# SEAx_connector.net
KiCad netlist of a schematic drawn in Altium Designer
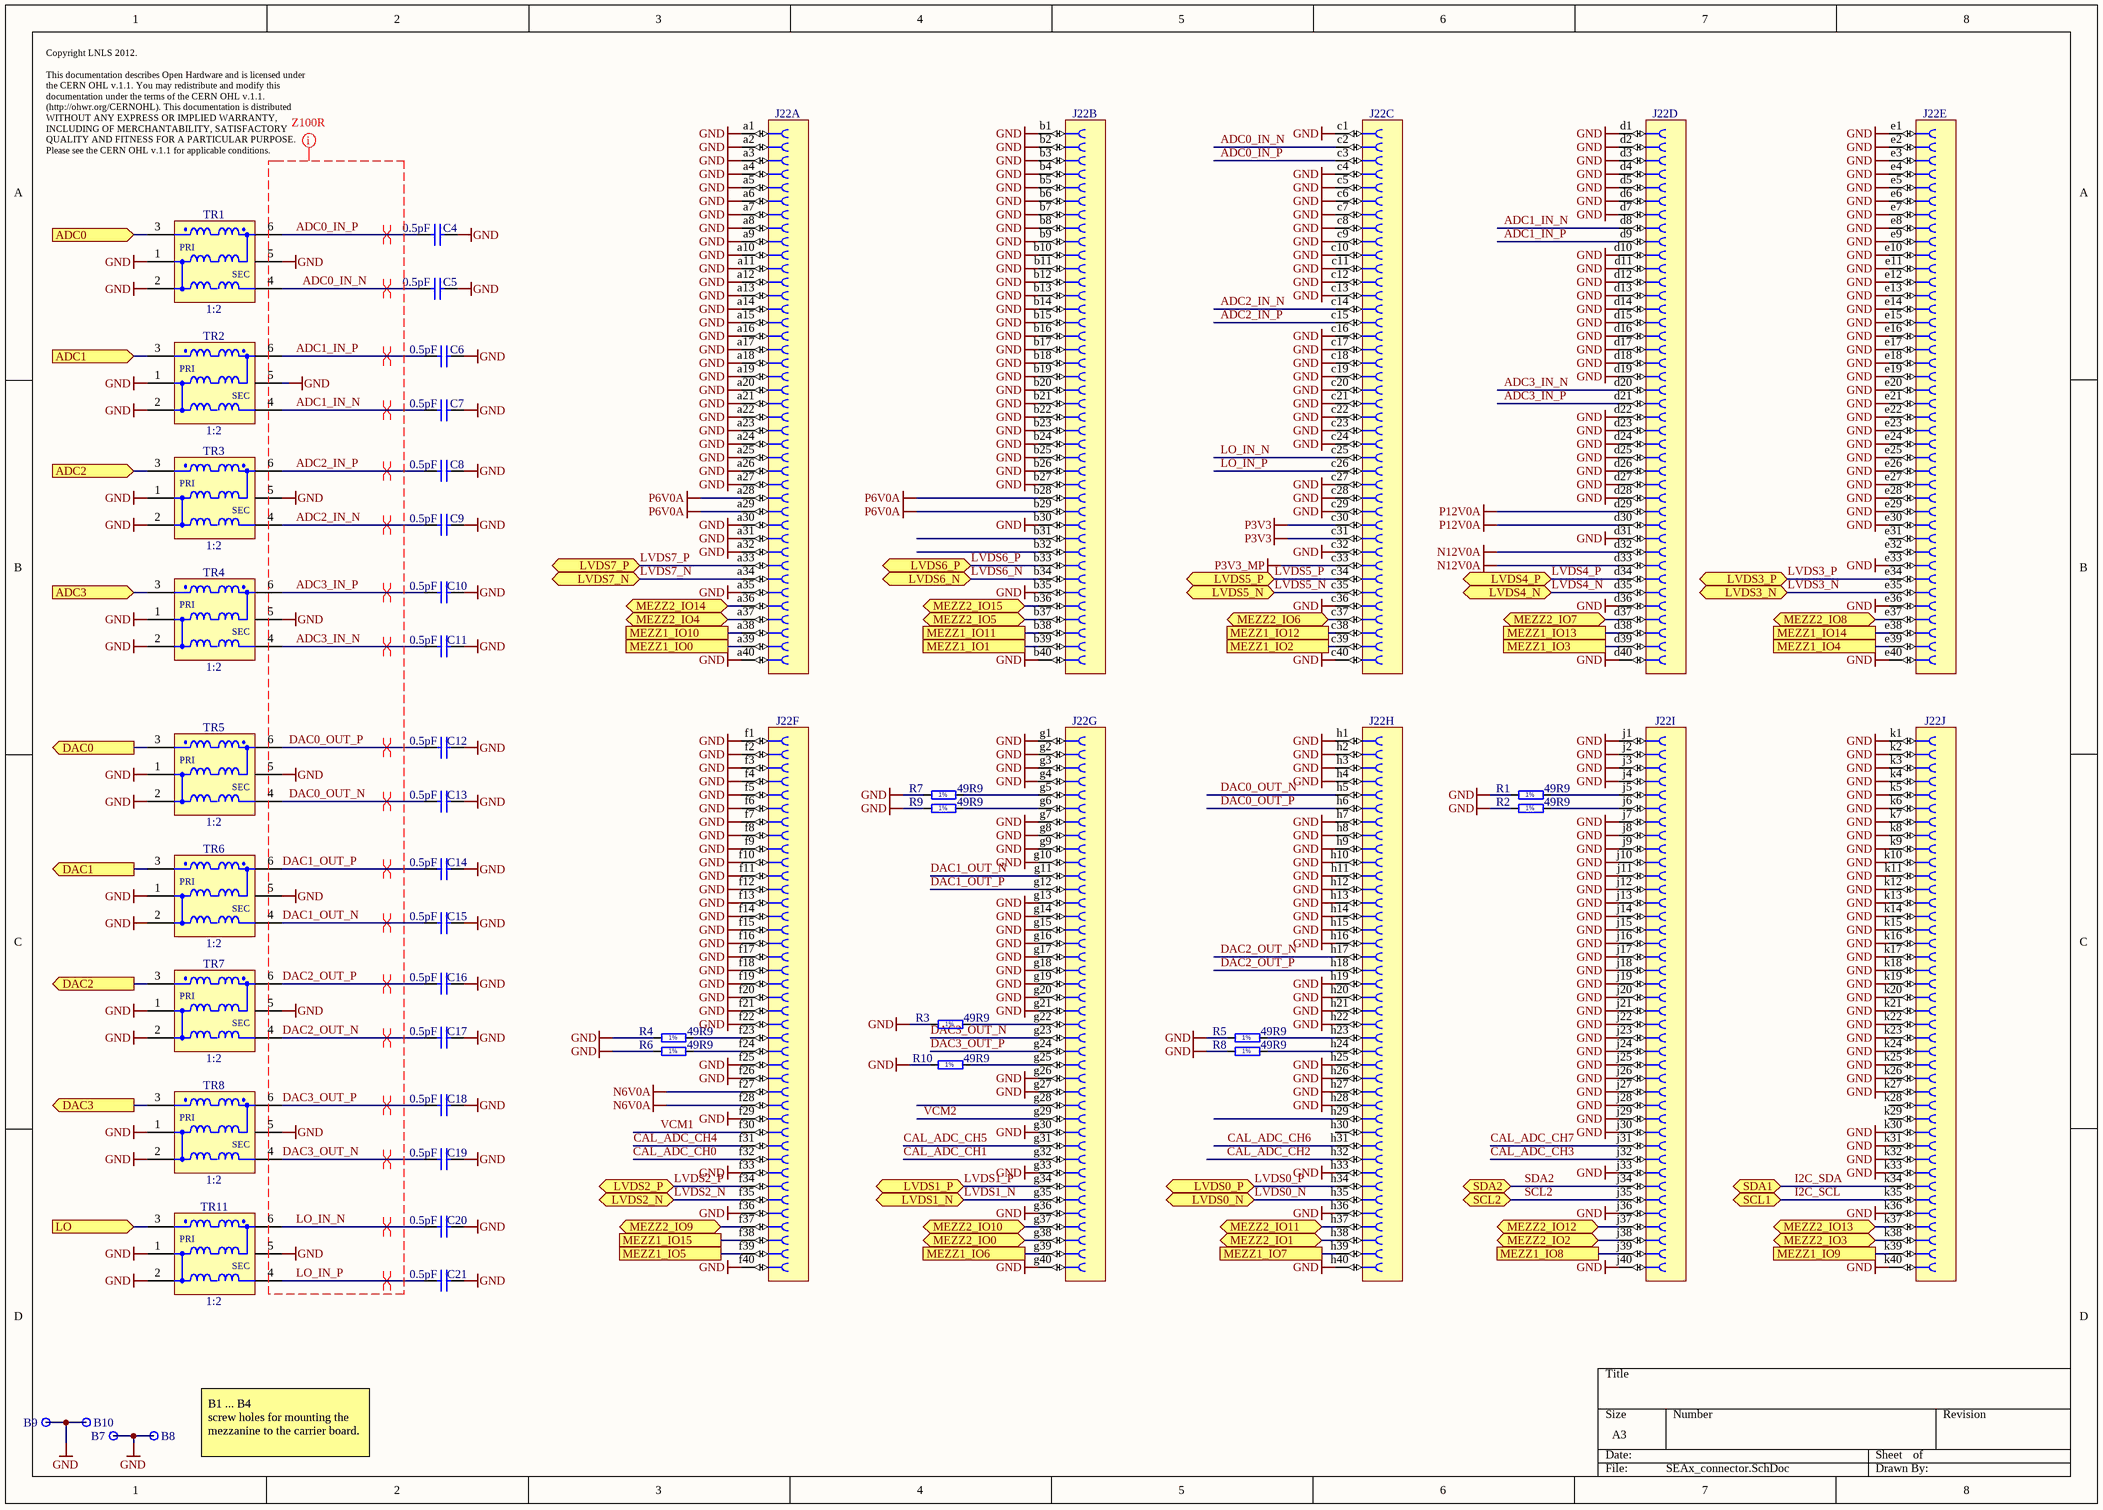
[diagram p0: SEAx_connector.SchDoc]

(export (version "E")
  (design (tool "Eeschema 10.0.6"))
  (components
    (comp (ref "B7")
      (value "Plated Hole")
      (footprint "MTG270_500")
      (description "Single Terminal Socket")
      (fields (field (name "PART NUMBER") "PLATED_HOLE2.7_PAD5.0") (field (name "AUTHOR") "CERN DEM JMW"))
      (libsource (lib "Eletro-mechanical") (part "Single Terminal Socket"))
    )
    (comp (ref "B8")
      (value "Plated Hole")
      (footprint "MTG270_500")
      (description "Single Terminal Socket")
      (fields (field (name "PART NUMBER") "PLATED_HOLE2.7_PAD5.0") (field (name "AUTHOR") "CERN DEM JMW"))
      (libsource (lib "Eletro-mechanical") (part "Single Terminal Socket"))
    )
    (comp (ref "B9")
      (value "Plated Hole")
      (footprint "MTG270_500")
      (description "Single Terminal Socket")
      (fields (field (name "PART NUMBER") "PLATED_HOLE2.7_PAD5.0") (field (name "AUTHOR") "CERN DEM JMW"))
      (libsource (lib "Eletro-mechanical") (part "Single Terminal Socket"))
    )
    (comp (ref "B10")
      (value "Plated Hole")
      (footprint "MTG270_500")
      (description "Single Terminal Socket")
      (fields (field (name "PART NUMBER") "PLATED_HOLE2.7_PAD5.0") (field (name "AUTHOR") "CERN DEM JMW"))
      (libsource (lib "Eletro-mechanical") (part "Single Terminal Socket"))
    )
    (comp (ref "C4")
      (value "0.5pF")
      (footprint "CAPC1005X50N")
      (description "Non-polarised capacitor")
      (fields
        (field (name "PART NUMBER") "CC0402_0.5PF_25V_0.05PF_AVX_04023J0R5ABSTR")
        (field (name "VOLTAGE") "25V")
        (field (name "AUTHOR") "CERN DEM JLC")
      )
      (libsource (lib "Capacitors") (part "Capacitor - non polarized"))
    )
    (comp (ref "C5")
      (value "0.5pF")
      (footprint "CAPC1005X50N")
      (description "Non-polarised capacitor")
      (fields
        (field (name "PART NUMBER") "CC0402_0.5PF_25V_0.05PF_AVX_04023J0R5ABSTR")
        (field (name "VOLTAGE") "25V")
        (field (name "AUTHOR") "CERN DEM JLC")
      )
      (libsource (lib "Capacitors") (part "Capacitor - non polarized"))
    )
    (comp (ref "C6")
      (value "0.5pF")
      (footprint "CAPC1005X50N")
      (description "Non-polarised capacitor")
      (fields
        (field (name "PART NUMBER") "CC0402_0.5PF_25V_0.05PF_AVX_04023J0R5ABSTR")
        (field (name "VOLTAGE") "25V")
        (field (name "AUTHOR") "CERN DEM JLC")
      )
      (libsource (lib "Capacitors") (part "Capacitor - non polarized"))
    )
    (comp (ref "C7")
      (value "0.5pF")
      (footprint "CAPC1005X50N")
      (description "Non-polarised capacitor")
      (fields
        (field (name "PART NUMBER") "CC0402_0.5PF_25V_0.05PF_AVX_04023J0R5ABSTR")
        (field (name "VOLTAGE") "25V")
        (field (name "AUTHOR") "CERN DEM JLC")
      )
      (libsource (lib "Capacitors") (part "Capacitor - non polarized"))
    )
    (comp (ref "C8")
      (value "0.5pF")
      (footprint "CAPC1005X50N")
      (description "Non-polarised capacitor")
      (fields
        (field (name "PART NUMBER") "CC0402_0.5PF_25V_0.05PF_AVX_04023J0R5ABSTR")
        (field (name "VOLTAGE") "25V")
        (field (name "AUTHOR") "CERN DEM JLC")
      )
      (libsource (lib "Capacitors") (part "Capacitor - non polarized"))
    )
    (comp (ref "C9")
      (value "0.5pF")
      (footprint "CAPC1005X50N")
      (description "Non-polarised capacitor")
      (fields
        (field (name "PART NUMBER") "CC0402_0.5PF_25V_0.05PF_AVX_04023J0R5ABSTR")
        (field (name "VOLTAGE") "25V")
        (field (name "AUTHOR") "CERN DEM JLC")
      )
      (libsource (lib "Capacitors") (part "Capacitor - non polarized"))
    )
    (comp (ref "C10")
      (value "0.5pF")
      (footprint "CAPC1005X50N")
      (description "Non-polarised capacitor")
      (fields
        (field (name "PART NUMBER") "CC0402_0.5PF_25V_0.05PF_AVX_04023J0R5ABSTR")
        (field (name "VOLTAGE") "25V")
        (field (name "AUTHOR") "CERN DEM JLC")
      )
      (libsource (lib "Capacitors") (part "Capacitor - non polarized"))
    )
    (comp (ref "C11")
      (value "0.5pF")
      (footprint "CAPC1005X50N")
      (description "Non-polarised capacitor")
      (fields
        (field (name "PART NUMBER") "CC0402_0.5PF_25V_0.05PF_AVX_04023J0R5ABSTR")
        (field (name "VOLTAGE") "25V")
        (field (name "AUTHOR") "CERN DEM JLC")
      )
      (libsource (lib "Capacitors") (part "Capacitor - non polarized"))
    )
    (comp (ref "C12")
      (value "0.5pF")
      (footprint "CAPC1005X50N")
      (description "Non-polarised capacitor")
      (fields
        (field (name "PART NUMBER") "CC0402_0.5PF_25V_0.05PF_AVX_04023J0R5ABSTR")
        (field (name "VOLTAGE") "25V")
        (field (name "AUTHOR") "CERN DEM JLC")
      )
      (libsource (lib "Capacitors") (part "Capacitor - non polarized"))
    )
    (comp (ref "C13")
      (value "0.5pF")
      (footprint "CAPC1005X50N")
      (description "Non-polarised capacitor")
      (fields
        (field (name "PART NUMBER") "CC0402_0.5PF_25V_0.05PF_AVX_04023J0R5ABSTR")
        (field (name "VOLTAGE") "25V")
        (field (name "AUTHOR") "CERN DEM JLC")
      )
      (libsource (lib "Capacitors") (part "Capacitor - non polarized"))
    )
    (comp (ref "C14")
      (value "0.5pF")
      (footprint "CAPC1005X50N")
      (description "Non-polarised capacitor")
      (fields
        (field (name "PART NUMBER") "CC0402_0.5PF_25V_0.05PF_AVX_04023J0R5ABSTR")
        (field (name "VOLTAGE") "25V")
        (field (name "AUTHOR") "CERN DEM JLC")
      )
      (libsource (lib "Capacitors") (part "Capacitor - non polarized"))
    )
    (comp (ref "C15")
      (value "0.5pF")
      (footprint "CAPC1005X50N")
      (description "Non-polarised capacitor")
      (fields
        (field (name "PART NUMBER") "CC0402_0.5PF_25V_0.05PF_AVX_04023J0R5ABSTR")
        (field (name "VOLTAGE") "25V")
        (field (name "AUTHOR") "CERN DEM JLC")
      )
      (libsource (lib "Capacitors") (part "Capacitor - non polarized"))
    )
    (comp (ref "C16")
      (value "0.5pF")
      (footprint "CAPC1005X50N")
      (description "Non-polarised capacitor")
      (fields
        (field (name "PART NUMBER") "CC0402_0.5PF_25V_0.05PF_AVX_04023J0R5ABSTR")
        (field (name "VOLTAGE") "25V")
        (field (name "AUTHOR") "CERN DEM JLC")
      )
      (libsource (lib "Capacitors") (part "Capacitor - non polarized"))
    )
    (comp (ref "C17")
      (value "0.5pF")
      (footprint "CAPC1005X50N")
      (description "Non-polarised capacitor")
      (fields
        (field (name "PART NUMBER") "CC0402_0.5PF_25V_0.05PF_AVX_04023J0R5ABSTR")
        (field (name "VOLTAGE") "25V")
        (field (name "AUTHOR") "CERN DEM JLC")
      )
      (libsource (lib "Capacitors") (part "Capacitor - non polarized"))
    )
    (comp (ref "C18")
      (value "0.5pF")
      (footprint "CAPC1005X50N")
      (description "Non-polarised capacitor")
      (fields
        (field (name "PART NUMBER") "CC0402_0.5PF_25V_0.05PF_AVX_04023J0R5ABSTR")
        (field (name "VOLTAGE") "25V")
        (field (name "AUTHOR") "CERN DEM JLC")
      )
      (libsource (lib "Capacitors") (part "Capacitor - non polarized"))
    )
    (comp (ref "C19")
      (value "0.5pF")
      (footprint "CAPC1005X50N")
      (description "Non-polarised capacitor")
      (fields
        (field (name "PART NUMBER") "CC0402_0.5PF_25V_0.05PF_AVX_04023J0R5ABSTR")
        (field (name "VOLTAGE") "25V")
        (field (name "AUTHOR") "CERN DEM JLC")
      )
      (libsource (lib "Capacitors") (part "Capacitor - non polarized"))
    )
    (comp (ref "C20")
      (value "0.5pF")
      (footprint "CAPC1005X50N")
      (description "Non-polarised capacitor")
      (fields
        (field (name "PART NUMBER") "CC0402_0.5PF_25V_0.05PF_AVX_04023J0R5ABSTR")
        (field (name "VOLTAGE") "25V")
        (field (name "AUTHOR") "CERN DEM JLC")
      )
      (libsource (lib "Capacitors") (part "Capacitor - non polarized"))
    )
    (comp (ref "C21")
      (value "0.5pF")
      (footprint "CAPC1005X50N")
      (description "Non-polarised capacitor")
      (fields
        (field (name "PART NUMBER") "CC0402_0.5PF_25V_0.05PF_AVX_04023J0R5ABSTR")
        (field (name "VOLTAGE") "25V")
        (field (name "AUTHOR") "CERN DEM JLC")
      )
      (libsource (lib "Capacitors") (part "Capacitor - non polarized"))
    )
    (comp (ref "J22")
      (value "VITA 57")
      (footprint "SAMTEC_ASP-134486-01")
      (description "Connector VITA 57, 400 Female contacts in 10 row abcdefghj")
      (fields
        (field (name "PART NUMBER") "SAMTEC_ASP-134486-01")
        (field (name "MANUFACTURER") "SAMTEC")
        (field (name "AUTHOR") "CERN DEM JLC")
      )
      (libsource (lib "Connectors") (part "Connector VITA 57 400 Female (abcdefghjk)"))
    )
    (comp (ref "R1")
      (value "49R9")
      (footprint "RESC1005X40N")
      (description "Resistor - 1%")
      (fields
        (field (name "PART NUMBER") "R0402_49R9_1%_0.0625W_100PPM")
        (field (name "POWER") "0.0625W")
        (field (name "AUTHOR") "CERN DEM JLC")
      )
      (libsource (lib "Resistors") (part "Resistor - 1%"))
    )
    (comp (ref "R2")
      (value "49R9")
      (footprint "RESC1005X40N")
      (description "Resistor - 1%")
      (fields
        (field (name "PART NUMBER") "R0402_49R9_1%_0.0625W_100PPM")
        (field (name "POWER") "0.0625W")
        (field (name "AUTHOR") "CERN DEM JLC")
      )
      (libsource (lib "Resistors") (part "Resistor - 1%"))
    )
    (comp (ref "R3")
      (value "49R9")
      (footprint "RESC1005X40N")
      (description "Resistor - 1%")
      (fields
        (field (name "PART NUMBER") "R0402_49R9_1%_0.0625W_100PPM")
        (field (name "POWER") "0.0625W")
        (field (name "AUTHOR") "CERN DEM JLC")
      )
      (libsource (lib "Resistors") (part "Resistor - 1%"))
    )
    (comp (ref "R4")
      (value "49R9")
      (footprint "RESC1005X40N")
      (description "Resistor - 1%")
      (fields
        (field (name "PART NUMBER") "R0402_49R9_1%_0.0625W_100PPM")
        (field (name "POWER") "0.0625W")
        (field (name "AUTHOR") "CERN DEM JLC")
      )
      (libsource (lib "Resistors") (part "Resistor - 1%"))
    )
    (comp (ref "R5")
      (value "49R9")
      (footprint "RESC1005X40N")
      (description "Resistor - 1%")
      (fields
        (field (name "PART NUMBER") "R0402_49R9_1%_0.0625W_100PPM")
        (field (name "POWER") "0.0625W")
        (field (name "AUTHOR") "CERN DEM JLC")
      )
      (libsource (lib "Resistors") (part "Resistor - 1%"))
    )
    (comp (ref "R6")
      (value "49R9")
      (footprint "RESC1005X40N")
      (description "Resistor - 1%")
      (fields
        (field (name "PART NUMBER") "R0402_49R9_1%_0.0625W_100PPM")
        (field (name "POWER") "0.0625W")
        (field (name "AUTHOR") "CERN DEM JLC")
      )
      (libsource (lib "Resistors") (part "Resistor - 1%"))
    )
    (comp (ref "R7")
      (value "49R9")
      (footprint "RESC1005X40N")
      (description "Resistor - 1%")
      (fields
        (field (name "PART NUMBER") "R0402_49R9_1%_0.0625W_100PPM")
        (field (name "POWER") "0.0625W")
        (field (name "AUTHOR") "CERN DEM JLC")
      )
      (libsource (lib "Resistors") (part "Resistor - 1%"))
    )
    (comp (ref "R8")
      (value "49R9")
      (footprint "RESC1005X40N")
      (description "Resistor - 1%")
      (fields
        (field (name "PART NUMBER") "R0402_49R9_1%_0.0625W_100PPM")
        (field (name "POWER") "0.0625W")
        (field (name "AUTHOR") "CERN DEM JLC")
      )
      (libsource (lib "Resistors") (part "Resistor - 1%"))
    )
    (comp (ref "R9")
      (value "49R9")
      (footprint "RESC1005X40N")
      (description "Resistor - 1%")
      (fields
        (field (name "PART NUMBER") "R0402_49R9_1%_0.0625W_100PPM")
        (field (name "POWER") "0.0625W")
        (field (name "AUTHOR") "CERN DEM JLC")
      )
      (libsource (lib "Resistors") (part "Resistor - 1%"))
    )
    (comp (ref "R10")
      (value "49R9")
      (footprint "RESC1005X40N")
      (description "Resistor - 1%")
      (fields
        (field (name "PART NUMBER") "R0402_49R9_1%_0.0625W_100PPM")
        (field (name "POWER") "0.0625W")
        (field (name "AUTHOR") "CERN DEM JLC")
      )
      (libsource (lib "Resistors") (part "Resistor - 1%"))
    )
    (comp (ref "TR1")
      (value "1:2")
      (footprint "XFMR_MINI-CIRCUITS_DB1627")
      (description "50 OHMS 10 to 4000 MHz RF Transformer")
      (fields
        (field (name "PART NUMBER") "XFMR_MINI-CIRCUITS_TCM2-43X+")
        (field (name "POWER") "0.4W")
        (field (name "AUTHOR") "CERN DEM BC")
      )
      (libsource (lib "Inductors & Transformers") (part "XFMR_MINI-CIRCUITS_TCM2-43X"))
    )
    (comp (ref "TR2")
      (value "1:2")
      (footprint "XFMR_MINI-CIRCUITS_DB1627")
      (description "50 OHMS 10 to 4000 MHz RF Transformer")
      (fields
        (field (name "PART NUMBER") "XFMR_MINI-CIRCUITS_TCM2-43X+")
        (field (name "POWER") "0.4W")
        (field (name "AUTHOR") "CERN DEM BC")
      )
      (libsource (lib "Inductors & Transformers") (part "XFMR_MINI-CIRCUITS_TCM2-43X"))
    )
    (comp (ref "TR3")
      (value "1:2")
      (footprint "XFMR_MINI-CIRCUITS_DB1627")
      (description "50 OHMS 10 to 4000 MHz RF Transformer")
      (fields
        (field (name "PART NUMBER") "XFMR_MINI-CIRCUITS_TCM2-43X+")
        (field (name "POWER") "0.4W")
        (field (name "AUTHOR") "CERN DEM BC")
      )
      (libsource (lib "Inductors & Transformers") (part "XFMR_MINI-CIRCUITS_TCM2-43X"))
    )
    (comp (ref "TR4")
      (value "1:2")
      (footprint "XFMR_MINI-CIRCUITS_DB1627")
      (description "50 OHMS 10 to 4000 MHz RF Transformer")
      (fields
        (field (name "PART NUMBER") "XFMR_MINI-CIRCUITS_TCM2-43X+")
        (field (name "POWER") "0.4W")
        (field (name "AUTHOR") "CERN DEM BC")
      )
      (libsource (lib "Inductors & Transformers") (part "XFMR_MINI-CIRCUITS_TCM2-43X"))
    )
    (comp (ref "TR5")
      (value "1:2")
      (footprint "XFMR_MINI-CIRCUITS_DB1627")
      (description "50 OHMS 10 to 4000 MHz RF Transformer")
      (fields
        (field (name "PART NUMBER") "XFMR_MINI-CIRCUITS_TCM2-43X+")
        (field (name "POWER") "0.4W")
        (field (name "AUTHOR") "CERN DEM BC")
      )
      (libsource (lib "Inductors & Transformers") (part "XFMR_MINI-CIRCUITS_TCM2-43X"))
    )
    (comp (ref "TR6")
      (value "1:2")
      (footprint "XFMR_MINI-CIRCUITS_DB1627")
      (description "50 OHMS 10 to 4000 MHz RF Transformer")
      (fields
        (field (name "PART NUMBER") "XFMR_MINI-CIRCUITS_TCM2-43X+")
        (field (name "POWER") "0.4W")
        (field (name "AUTHOR") "CERN DEM BC")
      )
      (libsource (lib "Inductors & Transformers") (part "XFMR_MINI-CIRCUITS_TCM2-43X"))
    )
    (comp (ref "TR7")
      (value "1:2")
      (footprint "XFMR_MINI-CIRCUITS_DB1627")
      (description "50 OHMS 10 to 4000 MHz RF Transformer")
      (fields
        (field (name "PART NUMBER") "XFMR_MINI-CIRCUITS_TCM2-43X+")
        (field (name "POWER") "0.4W")
        (field (name "AUTHOR") "CERN DEM BC")
      )
      (libsource (lib "Inductors & Transformers") (part "XFMR_MINI-CIRCUITS_TCM2-43X"))
    )
    (comp (ref "TR8")
      (value "1:2")
      (footprint "XFMR_MINI-CIRCUITS_DB1627")
      (description "50 OHMS 10 to 4000 MHz RF Transformer")
      (fields
        (field (name "PART NUMBER") "XFMR_MINI-CIRCUITS_TCM2-43X+")
        (field (name "POWER") "0.4W")
        (field (name "AUTHOR") "CERN DEM BC")
      )
      (libsource (lib "Inductors & Transformers") (part "XFMR_MINI-CIRCUITS_TCM2-43X"))
    )
    (comp (ref "TR11")
      (value "1:2")
      (footprint "XFMR_MINI-CIRCUITS_DB1627")
      (description "50 OHMS 10 to 4000 MHz RF Transformer")
      (fields
        (field (name "PART NUMBER") "XFMR_MINI-CIRCUITS_TCM2-43X+")
        (field (name "POWER") "0.4W")
        (field (name "AUTHOR") "CERN DEM BC")
      )
      (libsource (lib "Inductors & Transformers") (part "XFMR_MINI-CIRCUITS_TCM2-43X"))
    )
  )
  (nets
    (net (code "1") (name "/ADC0") (class "Default")
      (node (ref "TR1") (pin "3") (pinfunction "P1_3") (pintype "passive"))
    )
    (net (code "2") (name "/ADC0_IN_N") (class "Default")
      (node (ref "C5") (pin "1") (pinfunction "1_1") (pintype "passive"))
      (node (ref "J22") (pin "c2") (pinfunction "c2_c2") (pintype "bidirectional"))
      (node (ref "TR1") (pin "4") (pinfunction "S1_4") (pintype "passive"))
    )
    (net (code "3") (name "/ADC0_IN_P") (class "Default")
      (node (ref "C4") (pin "1") (pinfunction "1_1") (pintype "passive"))
      (node (ref "J22") (pin "c3") (pinfunction "c3_c3") (pintype "bidirectional"))
      (node (ref "TR1") (pin "6") (pinfunction "S1_6") (pintype "passive"))
    )
    (net (code "4") (name "/ADC1") (class "Default")
      (node (ref "TR2") (pin "3") (pinfunction "P1_3") (pintype "passive"))
    )
    (net (code "5") (name "/ADC1_IN_N") (class "Default")
      (node (ref "C7") (pin "1") (pinfunction "1_1") (pintype "passive"))
      (node (ref "J22") (pin "d8") (pinfunction "d8_d8") (pintype "bidirectional"))
      (node (ref "TR2") (pin "4") (pinfunction "S1_4") (pintype "passive"))
    )
    (net (code "6") (name "/ADC1_IN_P") (class "Default")
      (node (ref "C6") (pin "1") (pinfunction "1_1") (pintype "passive"))
      (node (ref "J22") (pin "d9") (pinfunction "d9_d9") (pintype "bidirectional"))
      (node (ref "TR2") (pin "6") (pinfunction "S1_6") (pintype "passive"))
    )
    (net (code "7") (name "/ADC2") (class "Default")
      (node (ref "TR3") (pin "3") (pinfunction "P1_3") (pintype "passive"))
    )
    (net (code "8") (name "/ADC2_IN_N") (class "Default")
      (node (ref "C9") (pin "1") (pinfunction "1_1") (pintype "passive"))
      (node (ref "J22") (pin "c14") (pinfunction "c14_c14") (pintype "bidirectional"))
      (node (ref "TR3") (pin "4") (pinfunction "S1_4") (pintype "passive"))
    )
    (net (code "9") (name "/ADC2_IN_P") (class "Default")
      (node (ref "C8") (pin "1") (pinfunction "1_1") (pintype "passive"))
      (node (ref "J22") (pin "c15") (pinfunction "c15_c15") (pintype "bidirectional"))
      (node (ref "TR3") (pin "6") (pinfunction "S1_6") (pintype "passive"))
    )
    (net (code "10") (name "/ADC3") (class "Default")
      (node (ref "TR4") (pin "3") (pinfunction "P1_3") (pintype "passive"))
    )
    (net (code "11") (name "/ADC3_IN_N") (class "Default")
      (node (ref "C11") (pin "1") (pinfunction "1_1") (pintype "passive"))
      (node (ref "J22") (pin "d20") (pinfunction "d20_d20") (pintype "bidirectional"))
      (node (ref "TR4") (pin "4") (pinfunction "S1_4") (pintype "passive"))
    )
    (net (code "12") (name "/ADC3_IN_P") (class "Default")
      (node (ref "C10") (pin "1") (pinfunction "1_1") (pintype "passive"))
      (node (ref "J22") (pin "d21") (pinfunction "d21_d21") (pintype "bidirectional"))
      (node (ref "TR4") (pin "6") (pinfunction "S1_6") (pintype "passive"))
    )
    (net (code "14") (name "/CAL_ADC_CH0") (class "Default")
      (node (ref "J22") (pin "f32") (pinfunction "f32_f32") (pintype "bidirectional"))
    )
    (net (code "15") (name "/CAL_ADC_CH1") (class "Default")
      (node (ref "J22") (pin "g32") (pinfunction "g32_g32") (pintype "bidirectional"))
    )
    (net (code "16") (name "/CAL_ADC_CH2") (class "Default")
      (node (ref "J22") (pin "h32") (pinfunction "h32_h32") (pintype "bidirectional"))
    )
    (net (code "17") (name "/CAL_ADC_CH3") (class "Default")
      (node (ref "J22") (pin "j32") (pinfunction "j32_j32") (pintype "bidirectional"))
    )
    (net (code "18") (name "/CAL_ADC_CH4") (class "Default")
      (node (ref "J22") (pin "f31") (pinfunction "f31_f31") (pintype "bidirectional"))
    )
    (net (code "19") (name "/CAL_ADC_CH5") (class "Default")
      (node (ref "J22") (pin "g31") (pinfunction "g31_g31") (pintype "bidirectional"))
    )
    (net (code "20") (name "/CAL_ADC_CH6") (class "Default")
      (node (ref "J22") (pin "h31") (pinfunction "h31_h31") (pintype "bidirectional"))
    )
    (net (code "21") (name "/CAL_ADC_CH7") (class "Default")
      (node (ref "J22") (pin "j31") (pinfunction "j31_j31") (pintype "bidirectional"))
    )
    (net (code "22") (name "/DAC0") (class "Default")
      (node (ref "TR5") (pin "3") (pinfunction "P1_3") (pintype "passive"))
    )
    (net (code "23") (name "/DAC0_OUT_N") (class "Default")
      (node (ref "C13") (pin "1") (pinfunction "1_1") (pintype "passive"))
      (node (ref "J22") (pin "h5") (pinfunction "h5_h5") (pintype "bidirectional"))
      (node (ref "TR5") (pin "4") (pinfunction "S1_4") (pintype "passive"))
    )
    (net (code "24") (name "/DAC0_OUT_P") (class "Default")
      (node (ref "C12") (pin "1") (pinfunction "1_1") (pintype "passive"))
      (node (ref "J22") (pin "h6") (pinfunction "h6_h6") (pintype "bidirectional"))
      (node (ref "TR5") (pin "6") (pinfunction "S1_6") (pintype "passive"))
    )
    (net (code "25") (name "/DAC1") (class "Default")
      (node (ref "TR6") (pin "3") (pinfunction "P1_3") (pintype "passive"))
    )
    (net (code "26") (name "/DAC1_OUT_N") (class "Default")
      (node (ref "C15") (pin "1") (pinfunction "1_1") (pintype "passive"))
      (node (ref "J22") (pin "g11") (pinfunction "g11_g11") (pintype "bidirectional"))
      (node (ref "TR6") (pin "4") (pinfunction "S1_4") (pintype "passive"))
    )
    (net (code "27") (name "/DAC1_OUT_P") (class "Default")
      (node (ref "C14") (pin "1") (pinfunction "1_1") (pintype "passive"))
      (node (ref "J22") (pin "g12") (pinfunction "g12_g12") (pintype "bidirectional"))
      (node (ref "TR6") (pin "6") (pinfunction "S1_6") (pintype "passive"))
    )
    (net (code "28") (name "/DAC2") (class "Default")
      (node (ref "TR7") (pin "3") (pinfunction "P1_3") (pintype "passive"))
    )
    (net (code "29") (name "/DAC2_OUT_N") (class "Default")
      (node (ref "C17") (pin "1") (pinfunction "1_1") (pintype "passive"))
      (node (ref "J22") (pin "h17") (pinfunction "h17_h17") (pintype "bidirectional"))
      (node (ref "TR7") (pin "4") (pinfunction "S1_4") (pintype "passive"))
    )
    (net (code "30") (name "/DAC2_OUT_P") (class "Default")
      (node (ref "C16") (pin "1") (pinfunction "1_1") (pintype "passive"))
      (node (ref "J22") (pin "h18") (pinfunction "h18_h18") (pintype "bidirectional"))
      (node (ref "TR7") (pin "6") (pinfunction "S1_6") (pintype "passive"))
    )
    (net (code "31") (name "/DAC3") (class "Default")
      (node (ref "TR8") (pin "3") (pinfunction "P1_3") (pintype "passive"))
    )
    (net (code "32") (name "/DAC3_OUT_N") (class "Default")
      (node (ref "C19") (pin "1") (pinfunction "1_1") (pintype "passive"))
      (node (ref "J22") (pin "g23") (pinfunction "g23_g23") (pintype "bidirectional"))
      (node (ref "TR8") (pin "4") (pinfunction "S1_4") (pintype "passive"))
    )
    (net (code "33") (name "/DAC3_OUT_P") (class "Default")
      (node (ref "C18") (pin "1") (pinfunction "1_1") (pintype "passive"))
      (node (ref "J22") (pin "g24") (pinfunction "g24_g24") (pintype "bidirectional"))
      (node (ref "TR8") (pin "6") (pinfunction "S1_6") (pintype "passive"))
    )
    (net (code "34") (name "/I2C_SCL") (class "Default")
      (node (ref "J22") (pin "k35") (pinfunction "k35_k35") (pintype "bidirectional"))
    )
    (net (code "35") (name "/I2C_SDA") (class "Default")
      (node (ref "J22") (pin "k34") (pinfunction "k34_k34") (pintype "bidirectional"))
    )
    (net (code "36") (name "/LO") (class "Default")
      (node (ref "TR11") (pin "3") (pinfunction "P1_3") (pintype "passive"))
    )
    (net (code "37") (name "/LO_IN_N") (class "Default")
      (node (ref "C20") (pin "1") (pinfunction "1_1") (pintype "passive"))
      (node (ref "J22") (pin "c25") (pinfunction "c25_c25") (pintype "bidirectional"))
      (node (ref "TR11") (pin "6") (pinfunction "S1_6") (pintype "passive"))
    )
    (net (code "38") (name "/LO_IN_P") (class "Default")
      (node (ref "C21") (pin "1") (pinfunction "1_1") (pintype "passive"))
      (node (ref "J22") (pin "c26") (pinfunction "c26_c26") (pintype "bidirectional"))
      (node (ref "TR11") (pin "4") (pinfunction "S1_4") (pintype "passive"))
    )
    (net (code "39") (name "/LVDS0_N") (class "Default")
      (node (ref "J22") (pin "h35") (pinfunction "h35_h35") (pintype "bidirectional"))
    )
    (net (code "40") (name "/LVDS0_P") (class "Default")
      (node (ref "J22") (pin "h34") (pinfunction "h34_h34") (pintype "bidirectional"))
    )
    (net (code "41") (name "/LVDS1_N") (class "Default")
      (node (ref "J22") (pin "g35") (pinfunction "g35_g35") (pintype "bidirectional"))
    )
    (net (code "42") (name "/LVDS1_P") (class "Default")
      (node (ref "J22") (pin "g34") (pinfunction "g34_g34") (pintype "bidirectional"))
    )
    (net (code "43") (name "/LVDS2_N") (class "Default")
      (node (ref "J22") (pin "f35") (pinfunction "f35_f35") (pintype "bidirectional"))
    )
    (net (code "44") (name "/LVDS2_P") (class "Default")
      (node (ref "J22") (pin "f34") (pinfunction "f34_f34") (pintype "bidirectional"))
    )
    (net (code "45") (name "/LVDS3_N") (class "Default")
      (node (ref "J22") (pin "e35") (pinfunction "e35_e35") (pintype "bidirectional"))
    )
    (net (code "46") (name "/LVDS3_P") (class "Default")
      (node (ref "J22") (pin "e34") (pinfunction "e34_e34") (pintype "bidirectional"))
    )
    (net (code "47") (name "/LVDS4_N") (class "Default")
      (node (ref "J22") (pin "d35") (pinfunction "d35_d35") (pintype "bidirectional"))
    )
    (net (code "48") (name "/LVDS4_P") (class "Default")
      (node (ref "J22") (pin "d34") (pinfunction "d34_d34") (pintype "bidirectional"))
    )
    (net (code "49") (name "/LVDS5_N") (class "Default")
      (node (ref "J22") (pin "c35") (pinfunction "c35_c35") (pintype "bidirectional"))
    )
    (net (code "50") (name "/LVDS5_P") (class "Default")
      (node (ref "J22") (pin "c34") (pinfunction "c34_c34") (pintype "bidirectional"))
    )
    (net (code "51") (name "/LVDS6_N") (class "Default")
      (node (ref "J22") (pin "b34") (pinfunction "b34_b34") (pintype "bidirectional"))
    )
    (net (code "52") (name "/LVDS6_P") (class "Default")
      (node (ref "J22") (pin "b33") (pinfunction "b33_b33") (pintype "bidirectional"))
    )
    (net (code "53") (name "/LVDS7_N") (class "Default")
      (node (ref "J22") (pin "a34") (pinfunction "a34_a34") (pintype "bidirectional"))
    )
    (net (code "54") (name "/LVDS7_P") (class "Default")
      (node (ref "J22") (pin "a33") (pinfunction "a33_a33") (pintype "bidirectional"))
    )
    (net (code "55") (name "/MEZZ1_IO0") (class "Default")
      (node (ref "J22") (pin "a39") (pinfunction "a39_a39") (pintype "bidirectional"))
    )
    (net (code "56") (name "/MEZZ1_IO1") (class "Default")
      (node (ref "J22") (pin "b39") (pinfunction "b39_b39") (pintype "bidirectional"))
    )
    (net (code "57") (name "/MEZZ1_IO2") (class "Default")
      (node (ref "J22") (pin "c39") (pinfunction "c39_c39") (pintype "bidirectional"))
    )
    (net (code "58") (name "/MEZZ1_IO3") (class "Default")
      (node (ref "J22") (pin "d39") (pinfunction "d39_d39") (pintype "bidirectional"))
    )
    (net (code "59") (name "/MEZZ1_IO4") (class "Default")
      (node (ref "J22") (pin "e39") (pinfunction "e39_e39") (pintype "bidirectional"))
    )
    (net (code "60") (name "/MEZZ1_IO5") (class "Default")
      (node (ref "J22") (pin "f39") (pinfunction "f39_f39") (pintype "bidirectional"))
    )
    (net (code "61") (name "/MEZZ1_IO6") (class "Default")
      (node (ref "J22") (pin "g39") (pinfunction "g39_g39") (pintype "bidirectional"))
    )
    (net (code "62") (name "/MEZZ1_IO7") (class "Default")
      (node (ref "J22") (pin "h39") (pinfunction "h39_h39") (pintype "bidirectional"))
    )
    (net (code "63") (name "/MEZZ1_IO8") (class "Default")
      (node (ref "J22") (pin "j39") (pinfunction "j39_j39") (pintype "bidirectional"))
    )
    (net (code "64") (name "/MEZZ1_IO9") (class "Default")
      (node (ref "J22") (pin "k39") (pinfunction "k39_k39") (pintype "bidirectional"))
    )
    (net (code "65") (name "/MEZZ1_IO10") (class "Default")
      (node (ref "J22") (pin "a38") (pinfunction "a38_a38") (pintype "bidirectional"))
    )
    (net (code "66") (name "/MEZZ1_IO11") (class "Default")
      (node (ref "J22") (pin "b38") (pinfunction "b38_b38") (pintype "bidirectional"))
    )
    (net (code "67") (name "/MEZZ1_IO12") (class "Default")
      (node (ref "J22") (pin "c38") (pinfunction "c38_c38") (pintype "bidirectional"))
    )
    (net (code "68") (name "/MEZZ1_IO13") (class "Default")
      (node (ref "J22") (pin "d38") (pinfunction "d38_d38") (pintype "bidirectional"))
    )
    (net (code "69") (name "/MEZZ1_IO14") (class "Default")
      (node (ref "J22") (pin "e38") (pinfunction "e38_e38") (pintype "bidirectional"))
    )
    (net (code "70") (name "/MEZZ1_IO15") (class "Default")
      (node (ref "J22") (pin "f38") (pinfunction "f38_f38") (pintype "bidirectional"))
    )
    (net (code "71") (name "/MEZZ2_IO0") (class "Default")
      (node (ref "J22") (pin "g38") (pinfunction "g38_g38") (pintype "bidirectional"))
    )
    (net (code "72") (name "/MEZZ2_IO1") (class "Default")
      (node (ref "J22") (pin "h38") (pinfunction "h38_h38") (pintype "bidirectional"))
    )
    (net (code "73") (name "/MEZZ2_IO2") (class "Default")
      (node (ref "J22") (pin "j38") (pinfunction "j38_j38") (pintype "bidirectional"))
    )
    (net (code "74") (name "/MEZZ2_IO3") (class "Default")
      (node (ref "J22") (pin "k38") (pinfunction "k38_k38") (pintype "bidirectional"))
    )
    (net (code "75") (name "/MEZZ2_IO4") (class "Default")
      (node (ref "J22") (pin "a37") (pinfunction "a37_a37") (pintype "bidirectional"))
    )
    (net (code "76") (name "/MEZZ2_IO5") (class "Default")
      (node (ref "J22") (pin "b37") (pinfunction "b37_b37") (pintype "bidirectional"))
    )
    (net (code "77") (name "/MEZZ2_IO6") (class "Default")
      (node (ref "J22") (pin "c37") (pinfunction "c37_c37") (pintype "bidirectional"))
    )
    (net (code "78") (name "/MEZZ2_IO7") (class "Default")
      (node (ref "J22") (pin "d37") (pinfunction "d37_d37") (pintype "bidirectional"))
    )
    (net (code "79") (name "/MEZZ2_IO8") (class "Default")
      (node (ref "J22") (pin "e37") (pinfunction "e37_e37") (pintype "bidirectional"))
    )
    (net (code "80") (name "/MEZZ2_IO9") (class "Default")
      (node (ref "J22") (pin "f37") (pinfunction "f37_f37") (pintype "bidirectional"))
    )
    (net (code "81") (name "/MEZZ2_IO10") (class "Default")
      (node (ref "J22") (pin "g37") (pinfunction "g37_g37") (pintype "bidirectional"))
    )
    (net (code "82") (name "/MEZZ2_IO11") (class "Default")
      (node (ref "J22") (pin "h37") (pinfunction "h37_h37") (pintype "bidirectional"))
    )
    (net (code "83") (name "/MEZZ2_IO12") (class "Default")
      (node (ref "J22") (pin "j37") (pinfunction "j37_j37") (pintype "bidirectional"))
    )
    (net (code "84") (name "/MEZZ2_IO13") (class "Default")
      (node (ref "J22") (pin "k37") (pinfunction "k37_k37") (pintype "bidirectional"))
    )
    (net (code "85") (name "/MEZZ2_IO14") (class "Default")
      (node (ref "J22") (pin "a36") (pinfunction "a36_a36") (pintype "bidirectional"))
    )
    (net (code "86") (name "/MEZZ2_IO15") (class "Default")
      (node (ref "J22") (pin "b36") (pinfunction "b36_b36") (pintype "bidirectional"))
    )
    (net (code "87") (name "/SCL2") (class "Default")
      (node (ref "J22") (pin "j35") (pinfunction "j35_j35") (pintype "bidirectional"))
    )
    (net (code "88") (name "/SDA2") (class "Default")
      (node (ref "J22") (pin "j34") (pinfunction "j34_j34") (pintype "bidirectional"))
    )
    (net (code "89") (name "/VCM1") (class "Default")
      (node (ref "J22") (pin "f30") (pinfunction "f30_f30") (pintype "bidirectional"))
    )
    (net (code "90") (name "/VCM2") (class "Default")
      (node (ref "J22") (pin "g29") (pinfunction "g29_g29") (pintype "bidirectional"))
    )
    (net (code "91") (name "GND") (class "Default")
      (node (ref "B10") (pin "1") (pinfunction "1_1") (pintype "bidirectional"))
      (node (ref "B7") (pin "1") (pinfunction "1_1") (pintype "bidirectional"))
      (node (ref "B8") (pin "1") (pinfunction "1_1") (pintype "bidirectional"))
      (node (ref "B9") (pin "1") (pinfunction "1_1") (pintype "bidirectional"))
      (node (ref "C10") (pin "2") (pinfunction "2_2") (pintype "passive"))
      (node (ref "C11") (pin "2") (pinfunction "2_2") (pintype "passive"))
      (node (ref "C12") (pin "2") (pinfunction "2_2") (pintype "passive"))
      (node (ref "C13") (pin "2") (pinfunction "2_2") (pintype "passive"))
      (node (ref "C14") (pin "2") (pinfunction "2_2") (pintype "passive"))
      (node (ref "C15") (pin "2") (pinfunction "2_2") (pintype "passive"))
      (node (ref "C16") (pin "2") (pinfunction "2_2") (pintype "passive"))
      (node (ref "C17") (pin "2") (pinfunction "2_2") (pintype "passive"))
      (node (ref "C18") (pin "2") (pinfunction "2_2") (pintype "passive"))
      (node (ref "C19") (pin "2") (pinfunction "2_2") (pintype "passive"))
      (node (ref "C20") (pin "2") (pinfunction "2_2") (pintype "passive"))
      (node (ref "C21") (pin "2") (pinfunction "2_2") (pintype "passive"))
      (node (ref "C4") (pin "2") (pinfunction "2_2") (pintype "passive"))
      (node (ref "C5") (pin "2") (pinfunction "2_2") (pintype "passive"))
      (node (ref "C6") (pin "2") (pinfunction "2_2") (pintype "passive"))
      (node (ref "C7") (pin "2") (pinfunction "2_2") (pintype "passive"))
      (node (ref "C8") (pin "2") (pinfunction "2_2") (pintype "passive"))
      (node (ref "C9") (pin "2") (pinfunction "2_2") (pintype "passive"))
      (node (ref "J22") (pin "a1") (pinfunction "a1_a1") (pintype "bidirectional"))
      (node (ref "J22") (pin "a10") (pinfunction "a10_a10") (pintype "bidirectional"))
      (node (ref "J22") (pin "a11") (pinfunction "a11_a11") (pintype "bidirectional"))
      (node (ref "J22") (pin "a12") (pinfunction "a12_a12") (pintype "bidirectional"))
      (node (ref "J22") (pin "a13") (pinfunction "a13_a13") (pintype "bidirectional"))
      (node (ref "J22") (pin "a14") (pinfunction "a14_a14") (pintype "bidirectional"))
      (node (ref "J22") (pin "a15") (pinfunction "a15_a15") (pintype "bidirectional"))
      (node (ref "J22") (pin "a16") (pinfunction "a16_a16") (pintype "bidirectional"))
      (node (ref "J22") (pin "a17") (pinfunction "a17_a17") (pintype "bidirectional"))
      (node (ref "J22") (pin "a18") (pinfunction "a18_a18") (pintype "bidirectional"))
      (node (ref "J22") (pin "a19") (pinfunction "a19_a19") (pintype "bidirectional"))
      (node (ref "J22") (pin "a2") (pinfunction "a2_a2") (pintype "bidirectional"))
      (node (ref "J22") (pin "a20") (pinfunction "a20_a20") (pintype "bidirectional"))
      (node (ref "J22") (pin "a21") (pinfunction "a21_a21") (pintype "bidirectional"))
      (node (ref "J22") (pin "a22") (pinfunction "a22_a22") (pintype "bidirectional"))
      (node (ref "J22") (pin "a23") (pinfunction "a23_a23") (pintype "bidirectional"))
      (node (ref "J22") (pin "a24") (pinfunction "a24_a24") (pintype "bidirectional"))
      (node (ref "J22") (pin "a25") (pinfunction "a25_a25") (pintype "bidirectional"))
      (node (ref "J22") (pin "a26") (pinfunction "a26_a26") (pintype "bidirectional"))
      (node (ref "J22") (pin "a27") (pinfunction "a27_a27") (pintype "bidirectional"))
      (node (ref "J22") (pin "a3") (pinfunction "a3_a3") (pintype "bidirectional"))
      (node (ref "J22") (pin "a30") (pinfunction "a30_a30") (pintype "bidirectional"))
      (node (ref "J22") (pin "a31") (pinfunction "a31_a31") (pintype "bidirectional"))
      (node (ref "J22") (pin "a32") (pinfunction "a32_a32") (pintype "bidirectional"))
      (node (ref "J22") (pin "a35") (pinfunction "a35_a35") (pintype "bidirectional"))
      (node (ref "J22") (pin "a4") (pinfunction "a4_a4") (pintype "bidirectional"))
      (node (ref "J22") (pin "a40") (pinfunction "a40_a40") (pintype "bidirectional"))
      (node (ref "J22") (pin "a5") (pinfunction "a5_a5") (pintype "bidirectional"))
      (node (ref "J22") (pin "a6") (pinfunction "a6_a6") (pintype "bidirectional"))
      (node (ref "J22") (pin "a7") (pinfunction "a7_a7") (pintype "bidirectional"))
      (node (ref "J22") (pin "a8") (pinfunction "a8_a8") (pintype "bidirectional"))
      (node (ref "J22") (pin "a9") (pinfunction "a9_a9") (pintype "bidirectional"))
      (node (ref "J22") (pin "b1") (pinfunction "b1_b1") (pintype "bidirectional"))
      (node (ref "J22") (pin "b10") (pinfunction "b10_b10") (pintype "bidirectional"))
      (node (ref "J22") (pin "b11") (pinfunction "b11_b11") (pintype "bidirectional"))
      (node (ref "J22") (pin "b12") (pinfunction "b12_b12") (pintype "bidirectional"))
      (node (ref "J22") (pin "b13") (pinfunction "b13_b13") (pintype "bidirectional"))
      (node (ref "J22") (pin "b14") (pinfunction "b14_b14") (pintype "bidirectional"))
      (node (ref "J22") (pin "b15") (pinfunction "b15_b15") (pintype "bidirectional"))
      (node (ref "J22") (pin "b16") (pinfunction "b16_b16") (pintype "bidirectional"))
      (node (ref "J22") (pin "b17") (pinfunction "b17_b17") (pintype "bidirectional"))
      (node (ref "J22") (pin "b18") (pinfunction "b18_b18") (pintype "bidirectional"))
      (node (ref "J22") (pin "b19") (pinfunction "b19_b19") (pintype "bidirectional"))
      (node (ref "J22") (pin "b2") (pinfunction "b2_b2") (pintype "bidirectional"))
      (node (ref "J22") (pin "b20") (pinfunction "b20_b20") (pintype "bidirectional"))
      (node (ref "J22") (pin "b21") (pinfunction "b21_b21") (pintype "bidirectional"))
      (node (ref "J22") (pin "b22") (pinfunction "b22_b22") (pintype "bidirectional"))
      (node (ref "J22") (pin "b23") (pinfunction "b23_b23") (pintype "bidirectional"))
      (node (ref "J22") (pin "b24") (pinfunction "b24_b24") (pintype "bidirectional"))
      (node (ref "J22") (pin "b25") (pinfunction "b25_b25") (pintype "bidirectional"))
      (node (ref "J22") (pin "b26") (pinfunction "b26_b26") (pintype "bidirectional"))
      (node (ref "J22") (pin "b27") (pinfunction "b27_b27") (pintype "bidirectional"))
      (node (ref "J22") (pin "b3") (pinfunction "b3_b3") (pintype "bidirectional"))
      (node (ref "J22") (pin "b30") (pinfunction "b30_b30") (pintype "bidirectional"))
      (node (ref "J22") (pin "b35") (pinfunction "b35_b35") (pintype "bidirectional"))
      (node (ref "J22") (pin "b4") (pinfunction "b4_b4") (pintype "bidirectional"))
      (node (ref "J22") (pin "b40") (pinfunction "b40_b40") (pintype "bidirectional"))
      (node (ref "J22") (pin "b5") (pinfunction "b5_b5") (pintype "bidirectional"))
      (node (ref "J22") (pin "b6") (pinfunction "b6_b6") (pintype "bidirectional"))
      (node (ref "J22") (pin "b7") (pinfunction "b7_b7") (pintype "bidirectional"))
      (node (ref "J22") (pin "b8") (pinfunction "b8_b8") (pintype "bidirectional"))
      (node (ref "J22") (pin "b9") (pinfunction "b9_b9") (pintype "bidirectional"))
      (node (ref "J22") (pin "c1") (pinfunction "c1_c1") (pintype "bidirectional"))
      (node (ref "J22") (pin "c10") (pinfunction "c10_c10") (pintype "bidirectional"))
      (node (ref "J22") (pin "c11") (pinfunction "c11_c11") (pintype "bidirectional"))
      (node (ref "J22") (pin "c12") (pinfunction "c12_c12") (pintype "bidirectional"))
      (node (ref "J22") (pin "c13") (pinfunction "c13_c13") (pintype "bidirectional"))
      (node (ref "J22") (pin "c16") (pinfunction "c16_c16") (pintype "bidirectional"))
      (node (ref "J22") (pin "c17") (pinfunction "c17_c17") (pintype "bidirectional"))
      (node (ref "J22") (pin "c18") (pinfunction "c18_c18") (pintype "bidirectional"))
      (node (ref "J22") (pin "c19") (pinfunction "c19_c19") (pintype "bidirectional"))
      (node (ref "J22") (pin "c20") (pinfunction "c20_c20") (pintype "bidirectional"))
      (node (ref "J22") (pin "c21") (pinfunction "c21_c21") (pintype "bidirectional"))
      (node (ref "J22") (pin "c22") (pinfunction "c22_c22") (pintype "bidirectional"))
      (node (ref "J22") (pin "c23") (pinfunction "c23_c23") (pintype "bidirectional"))
      (node (ref "J22") (pin "c24") (pinfunction "c24_c24") (pintype "bidirectional"))
      (node (ref "J22") (pin "c27") (pinfunction "c27_c27") (pintype "bidirectional"))
      (node (ref "J22") (pin "c28") (pinfunction "c28_c28") (pintype "bidirectional"))
      (node (ref "J22") (pin "c29") (pinfunction "c29_c29") (pintype "bidirectional"))
      (node (ref "J22") (pin "c32") (pinfunction "c32_c32") (pintype "bidirectional"))
      (node (ref "J22") (pin "c36") (pinfunction "c36_c36") (pintype "bidirectional"))
      (node (ref "J22") (pin "c4") (pinfunction "c4_c4") (pintype "bidirectional"))
      (node (ref "J22") (pin "c40") (pinfunction "c40_c40") (pintype "bidirectional"))
      (node (ref "J22") (pin "c5") (pinfunction "c5_c5") (pintype "bidirectional"))
      (node (ref "J22") (pin "c6") (pinfunction "c6_c6") (pintype "bidirectional"))
      (node (ref "J22") (pin "c7") (pinfunction "c7_c7") (pintype "bidirectional"))
      (node (ref "J22") (pin "c8") (pinfunction "c8_c8") (pintype "bidirectional"))
      (node (ref "J22") (pin "c9") (pinfunction "c9_c9") (pintype "bidirectional"))
      (node (ref "J22") (pin "d1") (pinfunction "d1_d1") (pintype "bidirectional"))
      (node (ref "J22") (pin "d10") (pinfunction "d10_d10") (pintype "bidirectional"))
      (node (ref "J22") (pin "d11") (pinfunction "d11_d11") (pintype "bidirectional"))
      (node (ref "J22") (pin "d12") (pinfunction "d12_d12") (pintype "bidirectional"))
      (node (ref "J22") (pin "d13") (pinfunction "d13_d13") (pintype "bidirectional"))
      (node (ref "J22") (pin "d14") (pinfunction "d14_d14") (pintype "bidirectional"))
      (node (ref "J22") (pin "d15") (pinfunction "d15_d15") (pintype "bidirectional"))
      (node (ref "J22") (pin "d16") (pinfunction "d16_d16") (pintype "bidirectional"))
      (node (ref "J22") (pin "d17") (pinfunction "d17_d17") (pintype "bidirectional"))
      (node (ref "J22") (pin "d18") (pinfunction "d18_d18") (pintype "bidirectional"))
      (node (ref "J22") (pin "d19") (pinfunction "d19_d19") (pintype "bidirectional"))
      (node (ref "J22") (pin "d2") (pinfunction "d2_d2") (pintype "bidirectional"))
      (node (ref "J22") (pin "d22") (pinfunction "d22_d22") (pintype "bidirectional"))
      (node (ref "J22") (pin "d23") (pinfunction "d23_d23") (pintype "bidirectional"))
      (node (ref "J22") (pin "d24") (pinfunction "d24_d24") (pintype "bidirectional"))
      (node (ref "J22") (pin "d25") (pinfunction "d25_d25") (pintype "bidirectional"))
      (node (ref "J22") (pin "d26") (pinfunction "d26_d26") (pintype "bidirectional"))
      (node (ref "J22") (pin "d27") (pinfunction "d27_d27") (pintype "bidirectional"))
      (node (ref "J22") (pin "d28") (pinfunction "d28_d28") (pintype "bidirectional"))
      (node (ref "J22") (pin "d3") (pinfunction "d3_d3") (pintype "bidirectional"))
      (node (ref "J22") (pin "d31") (pinfunction "d31_d31") (pintype "bidirectional"))
      (node (ref "J22") (pin "d36") (pinfunction "d36_d36") (pintype "bidirectional"))
      (node (ref "J22") (pin "d4") (pinfunction "d4_d4") (pintype "bidirectional"))
      (node (ref "J22") (pin "d40") (pinfunction "d40_d40") (pintype "bidirectional"))
      (node (ref "J22") (pin "d5") (pinfunction "d5_d5") (pintype "bidirectional"))
      (node (ref "J22") (pin "d6") (pinfunction "d6_d6") (pintype "bidirectional"))
      (node (ref "J22") (pin "d7") (pinfunction "d7_d7") (pintype "bidirectional"))
      (node (ref "J22") (pin "e1") (pinfunction "e1_e1") (pintype "bidirectional"))
      (node (ref "J22") (pin "e10") (pinfunction "e10_e10") (pintype "bidirectional"))
      (node (ref "J22") (pin "e11") (pinfunction "e11_e11") (pintype "bidirectional"))
      (node (ref "J22") (pin "e12") (pinfunction "e12_e12") (pintype "bidirectional"))
      (node (ref "J22") (pin "e13") (pinfunction "e13_e13") (pintype "bidirectional"))
      (node (ref "J22") (pin "e14") (pinfunction "e14_e14") (pintype "bidirectional"))
      (node (ref "J22") (pin "e15") (pinfunction "e15_e15") (pintype "bidirectional"))
      (node (ref "J22") (pin "e16") (pinfunction "e16_e16") (pintype "bidirectional"))
      (node (ref "J22") (pin "e17") (pinfunction "e17_e17") (pintype "bidirectional"))
      (node (ref "J22") (pin "e18") (pinfunction "e18_e18") (pintype "bidirectional"))
      (node (ref "J22") (pin "e19") (pinfunction "e19_e19") (pintype "bidirectional"))
      (node (ref "J22") (pin "e2") (pinfunction "e2_e2") (pintype "bidirectional"))
      (node (ref "J22") (pin "e20") (pinfunction "e20_e20") (pintype "bidirectional"))
      (node (ref "J22") (pin "e21") (pinfunction "e21_e21") (pintype "bidirectional"))
      (node (ref "J22") (pin "e22") (pinfunction "e22_e22") (pintype "bidirectional"))
      (node (ref "J22") (pin "e23") (pinfunction "e23_e23") (pintype "bidirectional"))
      (node (ref "J22") (pin "e24") (pinfunction "e24_e24") (pintype "bidirectional"))
      (node (ref "J22") (pin "e25") (pinfunction "e25_e25") (pintype "bidirectional"))
      (node (ref "J22") (pin "e26") (pinfunction "e26_e26") (pintype "bidirectional"))
      (node (ref "J22") (pin "e27") (pinfunction "e27_e27") (pintype "bidirectional"))
      (node (ref "J22") (pin "e28") (pinfunction "e28_e28") (pintype "bidirectional"))
      (node (ref "J22") (pin "e29") (pinfunction "e29_e29") (pintype "bidirectional"))
      (node (ref "J22") (pin "e3") (pinfunction "e3_e3") (pintype "bidirectional"))
      (node (ref "J22") (pin "e30") (pinfunction "e30_e30") (pintype "bidirectional"))
      (node (ref "J22") (pin "e33") (pinfunction "e33_e33") (pintype "bidirectional"))
      (node (ref "J22") (pin "e36") (pinfunction "e36_e36") (pintype "bidirectional"))
      (node (ref "J22") (pin "e4") (pinfunction "e4_e4") (pintype "bidirectional"))
      (node (ref "J22") (pin "e40") (pinfunction "e40_e40") (pintype "bidirectional"))
      (node (ref "J22") (pin "e5") (pinfunction "e5_e5") (pintype "bidirectional"))
      (node (ref "J22") (pin "e6") (pinfunction "e6_e6") (pintype "bidirectional"))
      (node (ref "J22") (pin "e7") (pinfunction "e7_e7") (pintype "bidirectional"))
      (node (ref "J22") (pin "e8") (pinfunction "e8_e8") (pintype "bidirectional"))
      (node (ref "J22") (pin "e9") (pinfunction "e9_e9") (pintype "bidirectional"))
      (node (ref "J22") (pin "f1") (pinfunction "f1_f1") (pintype "bidirectional"))
      (node (ref "J22") (pin "f10") (pinfunction "f10_f10") (pintype "bidirectional"))
      (node (ref "J22") (pin "f11") (pinfunction "f11_f11") (pintype "bidirectional"))
      (node (ref "J22") (pin "f12") (pinfunction "f12_f12") (pintype "bidirectional"))
      (node (ref "J22") (pin "f13") (pinfunction "f13_f13") (pintype "bidirectional"))
      (node (ref "J22") (pin "f14") (pinfunction "f14_f14") (pintype "bidirectional"))
      (node (ref "J22") (pin "f15") (pinfunction "f15_f15") (pintype "bidirectional"))
      (node (ref "J22") (pin "f16") (pinfunction "f16_f16") (pintype "bidirectional"))
      (node (ref "J22") (pin "f17") (pinfunction "f17_f17") (pintype "bidirectional"))
      (node (ref "J22") (pin "f18") (pinfunction "f18_f18") (pintype "bidirectional"))
      (node (ref "J22") (pin "f19") (pinfunction "f19_f19") (pintype "bidirectional"))
      (node (ref "J22") (pin "f2") (pinfunction "f2_f2") (pintype "bidirectional"))
      (node (ref "J22") (pin "f20") (pinfunction "f20_f20") (pintype "bidirectional"))
      (node (ref "J22") (pin "f21") (pinfunction "f21_f21") (pintype "bidirectional"))
      (node (ref "J22") (pin "f22") (pinfunction "f22_f22") (pintype "bidirectional"))
      (node (ref "J22") (pin "f25") (pinfunction "f25_f25") (pintype "bidirectional"))
      (node (ref "J22") (pin "f26") (pinfunction "f26_f26") (pintype "bidirectional"))
      (node (ref "J22") (pin "f29") (pinfunction "f29_f29") (pintype "bidirectional"))
      (node (ref "J22") (pin "f3") (pinfunction "f3_f3") (pintype "bidirectional"))
      (node (ref "J22") (pin "f33") (pinfunction "f33_f33") (pintype "bidirectional"))
      (node (ref "J22") (pin "f36") (pinfunction "f36_f36") (pintype "bidirectional"))
      (node (ref "J22") (pin "f4") (pinfunction "f4_f4") (pintype "bidirectional"))
      (node (ref "J22") (pin "f40") (pinfunction "f40_f40") (pintype "bidirectional"))
      (node (ref "J22") (pin "f5") (pinfunction "f5_f5") (pintype "bidirectional"))
      (node (ref "J22") (pin "f6") (pinfunction "f6_f6") (pintype "bidirectional"))
      (node (ref "J22") (pin "f7") (pinfunction "f7_f7") (pintype "bidirectional"))
      (node (ref "J22") (pin "f8") (pinfunction "f8_f8") (pintype "bidirectional"))
      (node (ref "J22") (pin "f9") (pinfunction "f9_f9") (pintype "bidirectional"))
      (node (ref "J22") (pin "g1") (pinfunction "g1_g1") (pintype "bidirectional"))
      (node (ref "J22") (pin "g10") (pinfunction "g10_g10") (pintype "bidirectional"))
      (node (ref "J22") (pin "g13") (pinfunction "g13_g13") (pintype "bidirectional"))
      (node (ref "J22") (pin "g14") (pinfunction "g14_g14") (pintype "bidirectional"))
      (node (ref "J22") (pin "g15") (pinfunction "g15_g15") (pintype "bidirectional"))
      (node (ref "J22") (pin "g16") (pinfunction "g16_g16") (pintype "bidirectional"))
      (node (ref "J22") (pin "g17") (pinfunction "g17_g17") (pintype "bidirectional"))
      (node (ref "J22") (pin "g18") (pinfunction "g18_g18") (pintype "bidirectional"))
      (node (ref "J22") (pin "g19") (pinfunction "g19_g19") (pintype "bidirectional"))
      (node (ref "J22") (pin "g2") (pinfunction "g2_g2") (pintype "bidirectional"))
      (node (ref "J22") (pin "g20") (pinfunction "g20_g20") (pintype "bidirectional"))
      (node (ref "J22") (pin "g21") (pinfunction "g21_g21") (pintype "bidirectional"))
      (node (ref "J22") (pin "g26") (pinfunction "g26_g26") (pintype "bidirectional"))
      (node (ref "J22") (pin "g27") (pinfunction "g27_g27") (pintype "bidirectional"))
      (node (ref "J22") (pin "g3") (pinfunction "g3_g3") (pintype "bidirectional"))
      (node (ref "J22") (pin "g30") (pinfunction "g30_g30") (pintype "bidirectional"))
      (node (ref "J22") (pin "g33") (pinfunction "g33_g33") (pintype "bidirectional"))
      (node (ref "J22") (pin "g36") (pinfunction "g36_g36") (pintype "bidirectional"))
      (node (ref "J22") (pin "g4") (pinfunction "g4_g4") (pintype "bidirectional"))
      (node (ref "J22") (pin "g40") (pinfunction "g40_g40") (pintype "bidirectional"))
      (node (ref "J22") (pin "g7") (pinfunction "g7_g7") (pintype "bidirectional"))
      (node (ref "J22") (pin "g8") (pinfunction "g8_g8") (pintype "bidirectional"))
      (node (ref "J22") (pin "g9") (pinfunction "g9_g9") (pintype "bidirectional"))
      (node (ref "J22") (pin "h1") (pinfunction "h1_h1") (pintype "bidirectional"))
      (node (ref "J22") (pin "h10") (pinfunction "h10_h10") (pintype "bidirectional"))
      (node (ref "J22") (pin "h11") (pinfunction "h11_h11") (pintype "bidirectional"))
      (node (ref "J22") (pin "h12") (pinfunction "h12_h12") (pintype "bidirectional"))
      (node (ref "J22") (pin "h13") (pinfunction "h13_h13") (pintype "bidirectional"))
      (node (ref "J22") (pin "h14") (pinfunction "h14_h14") (pintype "bidirectional"))
      (node (ref "J22") (pin "h15") (pinfunction "h15_h15") (pintype "bidirectional"))
      (node (ref "J22") (pin "h16") (pinfunction "h16_h16") (pintype "bidirectional"))
      (node (ref "J22") (pin "h19") (pinfunction "h19_h19") (pintype "bidirectional"))
      (node (ref "J22") (pin "h2") (pinfunction "h2_h2") (pintype "bidirectional"))
      (node (ref "J22") (pin "h20") (pinfunction "h20_h20") (pintype "bidirectional"))
      (node (ref "J22") (pin "h21") (pinfunction "h21_h21") (pintype "bidirectional"))
      (node (ref "J22") (pin "h22") (pinfunction "h22_h22") (pintype "bidirectional"))
      (node (ref "J22") (pin "h25") (pinfunction "h25_h25") (pintype "bidirectional"))
      (node (ref "J22") (pin "h26") (pinfunction "h26_h26") (pintype "bidirectional"))
      (node (ref "J22") (pin "h27") (pinfunction "h27_h27") (pintype "bidirectional"))
      (node (ref "J22") (pin "h28") (pinfunction "h28_h28") (pintype "bidirectional"))
      (node (ref "J22") (pin "h3") (pinfunction "h3_h3") (pintype "bidirectional"))
      (node (ref "J22") (pin "h33") (pinfunction "h33_h33") (pintype "bidirectional"))
      (node (ref "J22") (pin "h36") (pinfunction "h36_h36") (pintype "bidirectional"))
      (node (ref "J22") (pin "h4") (pinfunction "h4_h4") (pintype "bidirectional"))
      (node (ref "J22") (pin "h40") (pinfunction "h40_h40") (pintype "bidirectional"))
      (node (ref "J22") (pin "h7") (pinfunction "h7_h7") (pintype "bidirectional"))
      (node (ref "J22") (pin "h8") (pinfunction "h8_h8") (pintype "bidirectional"))
      (node (ref "J22") (pin "h9") (pinfunction "h9_h9") (pintype "bidirectional"))
      (node (ref "J22") (pin "j1") (pinfunction "j1_j1") (pintype "bidirectional"))
      (node (ref "J22") (pin "j10") (pinfunction "j10_j10") (pintype "bidirectional"))
      (node (ref "J22") (pin "j11") (pinfunction "j11_j11") (pintype "bidirectional"))
      (node (ref "J22") (pin "j12") (pinfunction "j12_j12") (pintype "bidirectional"))
      (node (ref "J22") (pin "j13") (pinfunction "j13_j13") (pintype "bidirectional"))
      (node (ref "J22") (pin "j14") (pinfunction "j14_j14") (pintype "bidirectional"))
      (node (ref "J22") (pin "j15") (pinfunction "j15_j15") (pintype "bidirectional"))
      (node (ref "J22") (pin "j16") (pinfunction "j16_j16") (pintype "bidirectional"))
      (node (ref "J22") (pin "j17") (pinfunction "j17_j17") (pintype "bidirectional"))
      (node (ref "J22") (pin "j18") (pinfunction "j18_j18") (pintype "bidirectional"))
      (node (ref "J22") (pin "j19") (pinfunction "j19_j19") (pintype "bidirectional"))
      (node (ref "J22") (pin "j2") (pinfunction "j2_j2") (pintype "bidirectional"))
      (node (ref "J22") (pin "j20") (pinfunction "j20_j20") (pintype "bidirectional"))
      (node (ref "J22") (pin "j21") (pinfunction "j21_j21") (pintype "bidirectional"))
      (node (ref "J22") (pin "j22") (pinfunction "j22_j22") (pintype "bidirectional"))
      (node (ref "J22") (pin "j23") (pinfunction "j23_j23") (pintype "bidirectional"))
      (node (ref "J22") (pin "j24") (pinfunction "j24_j24") (pintype "bidirectional"))
      (node (ref "J22") (pin "j25") (pinfunction "j25_j25") (pintype "bidirectional"))
      (node (ref "J22") (pin "j26") (pinfunction "j26_j26") (pintype "bidirectional"))
      (node (ref "J22") (pin "j27") (pinfunction "j27_j27") (pintype "bidirectional"))
      (node (ref "J22") (pin "j28") (pinfunction "j28_j28") (pintype "bidirectional"))
      (node (ref "J22") (pin "j29") (pinfunction "j29_j29") (pintype "bidirectional"))
      (node (ref "J22") (pin "j3") (pinfunction "j3_j3") (pintype "bidirectional"))
      (node (ref "J22") (pin "j30") (pinfunction "j30_j30") (pintype "bidirectional"))
      (node (ref "J22") (pin "j33") (pinfunction "j33_j33") (pintype "bidirectional"))
      (node (ref "J22") (pin "j36") (pinfunction "j36_j36") (pintype "bidirectional"))
      (node (ref "J22") (pin "j4") (pinfunction "j4_j4") (pintype "bidirectional"))
      (node (ref "J22") (pin "j40") (pinfunction "j40_j40") (pintype "bidirectional"))
      (node (ref "J22") (pin "j7") (pinfunction "j7_j7") (pintype "bidirectional"))
      (node (ref "J22") (pin "j8") (pinfunction "j8_j8") (pintype "bidirectional"))
      (node (ref "J22") (pin "j9") (pinfunction "j9_j9") (pintype "bidirectional"))
      (node (ref "J22") (pin "k1") (pinfunction "k1_k1") (pintype "bidirectional"))
      (node (ref "J22") (pin "k10") (pinfunction "k10_k10") (pintype "bidirectional"))
      (node (ref "J22") (pin "k11") (pinfunction "k11_k11") (pintype "bidirectional"))
      (node (ref "J22") (pin "k12") (pinfunction "k12_k12") (pintype "bidirectional"))
      (node (ref "J22") (pin "k13") (pinfunction "k13_k13") (pintype "bidirectional"))
      (node (ref "J22") (pin "k14") (pinfunction "k14_k14") (pintype "bidirectional"))
      (node (ref "J22") (pin "k15") (pinfunction "k15_k15") (pintype "bidirectional"))
      (node (ref "J22") (pin "k16") (pinfunction "k16_k16") (pintype "bidirectional"))
      (node (ref "J22") (pin "k17") (pinfunction "k17_k17") (pintype "bidirectional"))
      (node (ref "J22") (pin "k18") (pinfunction "k18_k18") (pintype "bidirectional"))
      (node (ref "J22") (pin "k19") (pinfunction "k19_k19") (pintype "bidirectional"))
      (node (ref "J22") (pin "k2") (pinfunction "k2_k2") (pintype "bidirectional"))
      (node (ref "J22") (pin "k20") (pinfunction "k20_k20") (pintype "bidirectional"))
      (node (ref "J22") (pin "k21") (pinfunction "k21_k21") (pintype "bidirectional"))
      (node (ref "J22") (pin "k22") (pinfunction "k22_k22") (pintype "bidirectional"))
      (node (ref "J22") (pin "k23") (pinfunction "k23_k23") (pintype "bidirectional"))
      (node (ref "J22") (pin "k24") (pinfunction "k24_k24") (pintype "bidirectional"))
      (node (ref "J22") (pin "k25") (pinfunction "k25_k25") (pintype "bidirectional"))
      (node (ref "J22") (pin "k26") (pinfunction "k26_k26") (pintype "bidirectional"))
      (node (ref "J22") (pin "k27") (pinfunction "k27_k27") (pintype "bidirectional"))
      (node (ref "J22") (pin "k3") (pinfunction "k3_k3") (pintype "bidirectional"))
      (node (ref "J22") (pin "k30") (pinfunction "k30_k30") (pintype "bidirectional"))
      (node (ref "J22") (pin "k31") (pinfunction "k31_k31") (pintype "bidirectional"))
      (node (ref "J22") (pin "k32") (pinfunction "k32_k32") (pintype "bidirectional"))
      (node (ref "J22") (pin "k33") (pinfunction "k33_k33") (pintype "bidirectional"))
      (node (ref "J22") (pin "k36") (pinfunction "k36_k36") (pintype "bidirectional"))
      (node (ref "J22") (pin "k4") (pinfunction "k4_k4") (pintype "bidirectional"))
      (node (ref "J22") (pin "k40") (pinfunction "k40_k40") (pintype "bidirectional"))
      (node (ref "J22") (pin "k5") (pinfunction "k5_k5") (pintype "bidirectional"))
      (node (ref "J22") (pin "k6") (pinfunction "k6_k6") (pintype "bidirectional"))
      (node (ref "J22") (pin "k7") (pinfunction "k7_k7") (pintype "bidirectional"))
      (node (ref "J22") (pin "k8") (pinfunction "k8_k8") (pintype "bidirectional"))
      (node (ref "J22") (pin "k9") (pinfunction "k9_k9") (pintype "bidirectional"))
      (node (ref "R1") (pin "1") (pinfunction "1_1") (pintype "passive"))
      (node (ref "R10") (pin "1") (pinfunction "1_1") (pintype "passive"))
      (node (ref "R2") (pin "1") (pinfunction "1_1") (pintype "passive"))
      (node (ref "R3") (pin "1") (pinfunction "1_1") (pintype "passive"))
      (node (ref "R4") (pin "1") (pinfunction "1_1") (pintype "passive"))
      (node (ref "R5") (pin "1") (pinfunction "1_1") (pintype "passive"))
      (node (ref "R6") (pin "1") (pinfunction "1_1") (pintype "passive"))
      (node (ref "R7") (pin "1") (pinfunction "1_1") (pintype "passive"))
      (node (ref "R8") (pin "1") (pinfunction "1_1") (pintype "passive"))
      (node (ref "R9") (pin "1") (pinfunction "1_1") (pintype "passive"))
      (node (ref "TR1") (pin "1") (pinfunction "P1_1") (pintype "passive"))
      (node (ref "TR1") (pin "2") (pinfunction "P1_2") (pintype "passive"))
      (node (ref "TR1") (pin "5") (pinfunction "NC_5") (pintype "passive"))
      (node (ref "TR11") (pin "1") (pinfunction "P1_1") (pintype "passive"))
      (node (ref "TR11") (pin "2") (pinfunction "P1_2") (pintype "passive"))
      (node (ref "TR11") (pin "5") (pinfunction "NC_5") (pintype "passive"))
      (node (ref "TR2") (pin "1") (pinfunction "P1_1") (pintype "passive"))
      (node (ref "TR2") (pin "2") (pinfunction "P1_2") (pintype "passive"))
      (node (ref "TR2") (pin "5") (pinfunction "NC_5") (pintype "passive"))
      (node (ref "TR3") (pin "1") (pinfunction "P1_1") (pintype "passive"))
      (node (ref "TR3") (pin "2") (pinfunction "P1_2") (pintype "passive"))
      (node (ref "TR3") (pin "5") (pinfunction "NC_5") (pintype "passive"))
      (node (ref "TR4") (pin "1") (pinfunction "P1_1") (pintype "passive"))
      (node (ref "TR4") (pin "2") (pinfunction "P1_2") (pintype "passive"))
      (node (ref "TR4") (pin "5") (pinfunction "NC_5") (pintype "passive"))
      (node (ref "TR5") (pin "1") (pinfunction "P1_1") (pintype "passive"))
      (node (ref "TR5") (pin "2") (pinfunction "P1_2") (pintype "passive"))
      (node (ref "TR5") (pin "5") (pinfunction "NC_5") (pintype "passive"))
      (node (ref "TR6") (pin "1") (pinfunction "P1_1") (pintype "passive"))
      (node (ref "TR6") (pin "2") (pinfunction "P1_2") (pintype "passive"))
      (node (ref "TR6") (pin "5") (pinfunction "NC_5") (pintype "passive"))
      (node (ref "TR7") (pin "1") (pinfunction "P1_1") (pintype "passive"))
      (node (ref "TR7") (pin "2") (pinfunction "P1_2") (pintype "passive"))
      (node (ref "TR7") (pin "5") (pinfunction "NC_5") (pintype "passive"))
      (node (ref "TR8") (pin "1") (pinfunction "P1_1") (pintype "passive"))
      (node (ref "TR8") (pin "2") (pinfunction "P1_2") (pintype "passive"))
      (node (ref "TR8") (pin "5") (pinfunction "NC_5") (pintype "passive"))
    )
    (net (code "92") (name "N6V0A") (class "Default")
      (node (ref "J22") (pin "f27") (pinfunction "f27_f27") (pintype "bidirectional"))
      (node (ref "J22") (pin "f28") (pinfunction "f28_f28") (pintype "bidirectional"))
    )
    (net (code "93") (name "N12V0A") (class "Default")
      (node (ref "J22") (pin "d32") (pinfunction "d32_d32") (pintype "bidirectional"))
      (node (ref "J22") (pin "d33") (pinfunction "d33_d33") (pintype "bidirectional"))
    )
    (net (code "94") (name "Net-(J22-Padf23)") (class "Default")
      (node (ref "J22") (pin "f23") (pinfunction "f23_f23") (pintype "bidirectional"))
      (node (ref "R4") (pin "2") (pinfunction "2_2") (pintype "passive"))
    )
    (net (code "95") (name "Net-(J22-Padf24)") (class "Default")
      (node (ref "J22") (pin "f24") (pinfunction "f24_f24") (pintype "bidirectional"))
      (node (ref "R6") (pin "2") (pinfunction "2_2") (pintype "passive"))
    )
    (net (code "96") (name "Net-(J22-Padg5)") (class "Default")
      (node (ref "J22") (pin "g5") (pinfunction "g5_g5") (pintype "bidirectional"))
      (node (ref "R7") (pin "2") (pinfunction "2_2") (pintype "passive"))
    )
    (net (code "97") (name "Net-(J22-Padg6)") (class "Default")
      (node (ref "J22") (pin "g6") (pinfunction "g6_g6") (pintype "bidirectional"))
      (node (ref "R9") (pin "2") (pinfunction "2_2") (pintype "passive"))
    )
    (net (code "98") (name "Net-(J22-Padg22)") (class "Default")
      (node (ref "J22") (pin "g22") (pinfunction "g22_g22") (pintype "bidirectional"))
      (node (ref "R3") (pin "2") (pinfunction "2_2") (pintype "passive"))
    )
    (net (code "99") (name "Net-(J22-Padg25)") (class "Default")
      (node (ref "J22") (pin "g25") (pinfunction "g25_g25") (pintype "bidirectional"))
      (node (ref "R10") (pin "2") (pinfunction "2_2") (pintype "passive"))
    )
    (net (code "100") (name "Net-(J22-Padh23)") (class "Default")
      (node (ref "J22") (pin "h23") (pinfunction "h23_h23") (pintype "bidirectional"))
      (node (ref "R5") (pin "2") (pinfunction "2_2") (pintype "passive"))
    )
    (net (code "101") (name "Net-(J22-Padh24)") (class "Default")
      (node (ref "J22") (pin "h24") (pinfunction "h24_h24") (pintype "bidirectional"))
      (node (ref "R8") (pin "2") (pinfunction "2_2") (pintype "passive"))
    )
    (net (code "102") (name "Net-(J22-Padj5)") (class "Default")
      (node (ref "J22") (pin "j5") (pinfunction "j5_j5") (pintype "bidirectional"))
      (node (ref "R1") (pin "2") (pinfunction "2_2") (pintype "passive"))
    )
    (net (code "103") (name "Net-(J22-Padj6)") (class "Default")
      (node (ref "J22") (pin "j6") (pinfunction "j6_j6") (pintype "bidirectional"))
      (node (ref "R2") (pin "2") (pinfunction "2_2") (pintype "passive"))
    )
    (net (code "104") (name "P3V3") (class "Default")
      (node (ref "J22") (pin "c30") (pinfunction "c30_c30") (pintype "bidirectional"))
      (node (ref "J22") (pin "c31") (pinfunction "c31_c31") (pintype "bidirectional"))
    )
    (net (code "105") (name "P3V3_MP") (class "Default")
      (node (ref "J22") (pin "c33") (pinfunction "c33_c33") (pintype "bidirectional"))
    )
    (net (code "106") (name "P6V0A") (class "Default")
      (node (ref "J22") (pin "a28") (pinfunction "a28_a28") (pintype "bidirectional"))
      (node (ref "J22") (pin "a29") (pinfunction "a29_a29") (pintype "bidirectional"))
      (node (ref "J22") (pin "b28") (pinfunction "b28_b28") (pintype "bidirectional"))
      (node (ref "J22") (pin "b29") (pinfunction "b29_b29") (pintype "bidirectional"))
    )
    (net (code "107") (name "P12V0A") (class "Default")
      (node (ref "J22") (pin "d29") (pinfunction "d29_d29") (pintype "bidirectional"))
      (node (ref "J22") (pin "d30") (pinfunction "d30_d30") (pintype "bidirectional"))
    )
    (net (code "108") (name "unconnected-(J22-Padb31)") (class "Default")
      (node (ref "J22") (pin "b31") (pinfunction "b31_b31") (pintype "bidirectional"))
    )
    (net (code "109") (name "unconnected-(J22-Padb32)") (class "Default")
      (node (ref "J22") (pin "b32") (pinfunction "b32_b32") (pintype "bidirectional"))
    )
    (net (code "110") (name "unconnected-(J22-Pade31)") (class "Default")
      (node (ref "J22") (pin "e31") (pinfunction "e31_e31") (pintype "bidirectional"))
    )
    (net (code "111") (name "unconnected-(J22-Pade32)") (class "Default")
      (node (ref "J22") (pin "e32") (pinfunction "e32_e32") (pintype "bidirectional"))
    )
    (net (code "112") (name "unconnected-(J22-Padg28)") (class "Default")
      (node (ref "J22") (pin "g28") (pinfunction "g28_g28") (pintype "bidirectional"))
    )
    (net (code "113") (name "unconnected-(J22-Padh29)") (class "Default")
      (node (ref "J22") (pin "h29") (pinfunction "h29_h29") (pintype "bidirectional"))
    )
    (net (code "114") (name "unconnected-(J22-Padh30)") (class "Default")
      (node (ref "J22") (pin "h30") (pinfunction "h30_h30") (pintype "bidirectional"))
    )
    (net (code "115") (name "unconnected-(J22-Padk28)") (class "Default")
      (node (ref "J22") (pin "k28") (pinfunction "k28_k28") (pintype "bidirectional"))
    )
    (net (code "116") (name "unconnected-(J22-Padk29)") (class "Default")
      (node (ref "J22") (pin "k29") (pinfunction "k29_k29") (pintype "bidirectional"))
    )
  )
)
